# ANALOG_IOUTPUT.net
KiCad netlist of a schematic drawn in Altium Designer
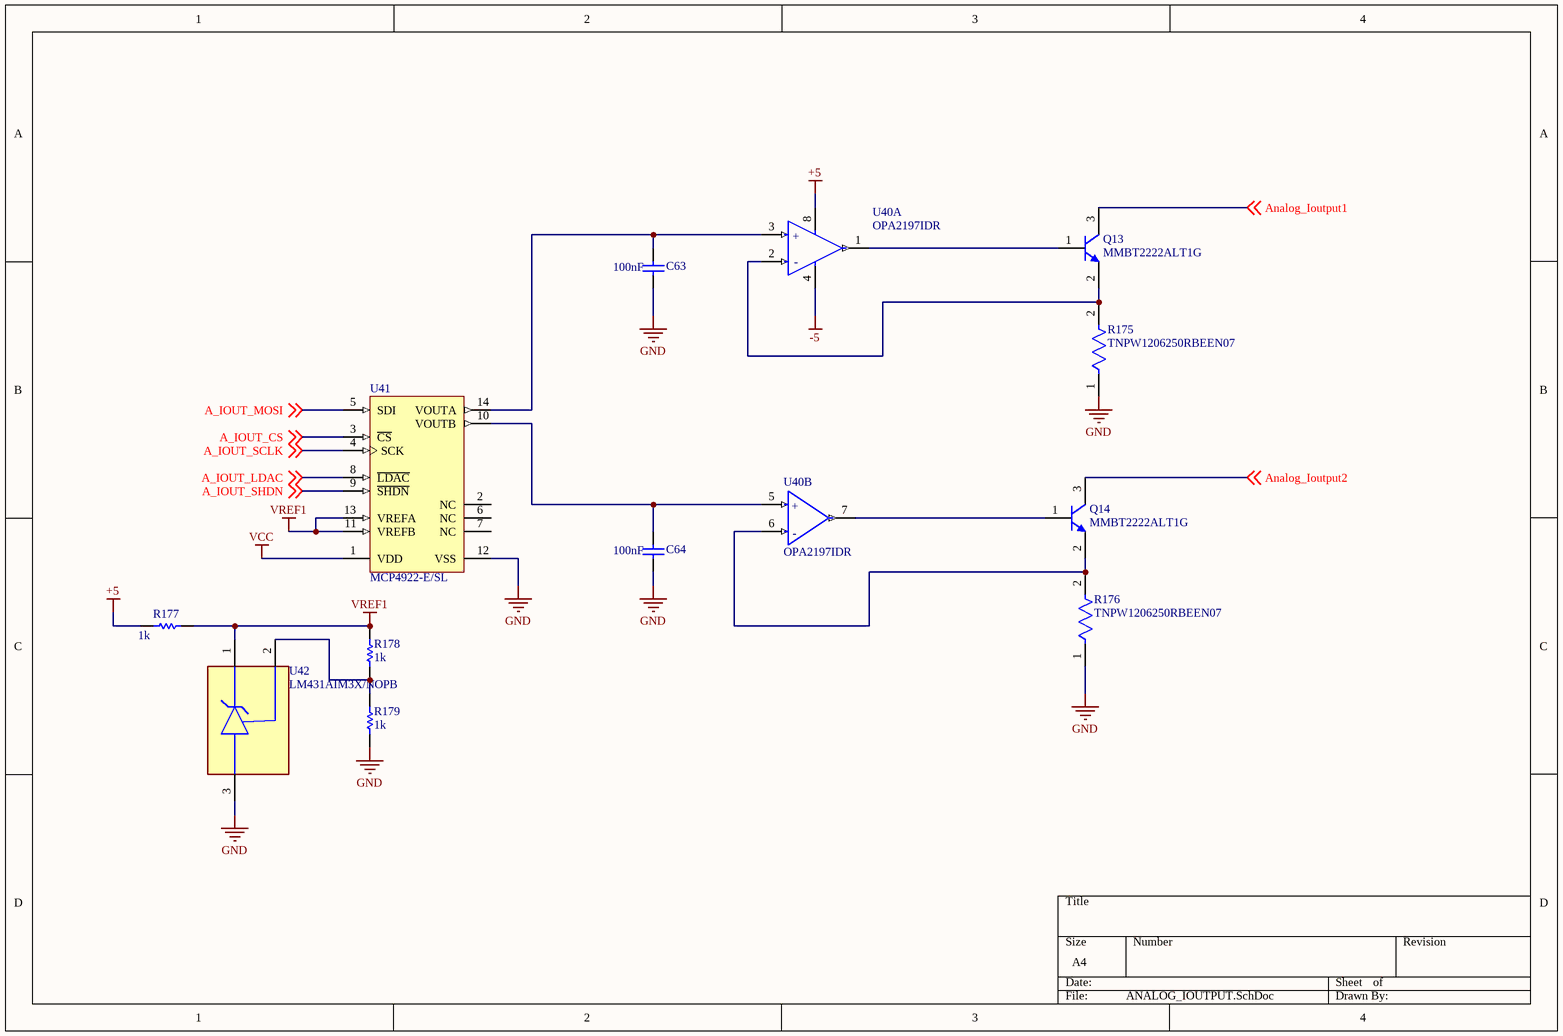
[diagram p0: ANALOG_IOUTPUT.SchDoc]

(export (version "E")
  (design (tool "Eeschema 10.0.6"))
  (components
    (comp (ref "C63")
      (value "GRM21BR71H104KA01L")
      (footprint "CAPC2013X135X45ML10T25")
      (description "Chip Capacitor, 0.1 uF, +/- 10%, 50 V, -55 to 125 degC, 0805 (2012 Metric), RoHS, Tape and Reel")
      (fields
        (field (name "VOLTAGE") "50V")
        (field (name "CAPACITANCE") "100nF")
        (field (name "TOLERANCE") "10%")
      )
      (libsource (lib "Altium Content Vault") (part "CAP-NP-2"))
    )
    (comp (ref "C64")
      (value "GRM21BR71H104KA01L")
      (footprint "CAPC2013X135X45ML10T25")
      (description "Chip Capacitor, 0.1 uF, +/- 10%, 50 V, -55 to 125 degC, 0805 (2012 Metric), RoHS, Tape and Reel")
      (fields
        (field (name "VOLTAGE") "50V")
        (field (name "CAPACITANCE") "100nF")
        (field (name "TOLERANCE") "10%")
      )
      (libsource (lib "Altium Content Vault") (part "CAP-NP-2"))
    )
    (comp (ref "Q13")
      (value "MMBT2222ALT1G")
      (footprint "ONSC-SOT-23-3-318-08_V")
      (description "General Purpose Transistor, NPN Silicon, 3-Pin SOT-23, Pb-Free, Tape and Reel")
      (fields (field (name "MANUFACTURER") "On Semiconductor"))
      (libsource (lib "Altium Content Vault") (part "ONSC-NPN-B1E2C3-3"))
    )
    (comp (ref "Q14")
      (value "MMBT2222ALT1G")
      (footprint "ONSC-SOT-23-3-318-08_V")
      (description "General Purpose Transistor, NPN Silicon, 3-Pin SOT-23, Pb-Free, Tape and Reel")
      (fields (field (name "MANUFACTURER") "On Semiconductor"))
      (libsource (lib "Altium Content Vault") (part "ONSC-NPN-B1E2C3-3"))
    )
    (comp (ref "R175")
      (value "TNPW1206250RBEEN07")
      (footprint "FP-TNPW1206-e3-MFG")
      (description "Res Thnflm 1206 250R Ohm 0.1% 1/4W 25PPM/C SMD")
      (fields (field (name "TOLERANCE") "0.1%"))
      (libsource (lib "Altium Content Vault") (part "1029c3af85768c4190bb7ad29bc67b5"))
    )
    (comp (ref "R176")
      (value "TNPW1206250RBEEN07")
      (footprint "FP-TNPW1206-e3-MFG")
      (description "Res Thnflm 1206 250R Ohm 0.1% 1/4W 25PPM/C SMD")
      (fields (field (name "TOLERANCE") "0.1%"))
      (libsource (lib "Altium Content Vault") (part "1029c3af85768c4190bb7ad29bc67b5"))
    )
    (comp (ref "R177")
      (value "1k")
      (footprint "RESC2013X50X30NL20T20")
      (fields (field (name "MANUFACTURER") "Vishay Dale") (field (name "PART NUMBER") "CRCW08051K00FKTC"))
      (libsource (lib "Altium Content Vault") (part "RES"))
    )
    (comp (ref "R178")
      (value "1k")
      (footprint "RESC2013X50X30NL20T20")
      (fields (field (name "MANUFACTURER") "Vishay Dale") (field (name "PART NUMBER") "CRCW08051K00FKTC"))
      (libsource (lib "Altium Content Vault") (part "RES"))
    )
    (comp (ref "R179")
      (value "1k")
      (footprint "RESC2013X50X30NL20T20")
      (fields (field (name "MANUFACTURER") "Vishay Dale") (field (name "PART NUMBER") "CRCW08051K00FKTC"))
      (libsource (lib "Altium Content Vault") (part "RES"))
    )
    (comp (ref "U40")
      (value "OPA2197IDR")
      (footprint "FP-D0008A-MFG")
      (description "IC OP AMP GP RR 10MHZ 8-SOIC")
      (fields
        (field (name "MANUFACTURER") "Texas Instruments")
        (field (name "OCTOPART") "https://octopart.com/opa2197idr-texas+instruments-75179702")
      )
      (libsource (lib "Altium Content Vault") (part "499df5fc91ff7ad023bcaf249d8becd"))
    )
    (comp (ref "U41")
      (value "MCP4922-E/SL")
      (footprint "SOIC-SL14_M")
      (description "12-Bit DAC with SPI Interface, 14-Pin SOIC 150mil, Extended Temperature")
      (libsource (lib "Altium Content Vault") (part "CON-DAC-MCP4922-14"))
    )
    (comp (ref "U42")
      (value "LM431AIM3X/NOPB")
      (footprint "FP-DBZ0003A-IPC_B")
      (description "IC VREF SHUNT 37V 2.2% SOT23-3")
      (fields (field (name "TOLERANCE") "2%"))
      (libsource (lib "Altium Content Vault") (part "493a0447014da16a84e61b4a2bbdac0"))
    )
  )
  (nets
    (net (code "1") (name "+5") (class "Default")
      (node (ref "R177") (pin "1") (pinfunction "1_1") (pintype "passive"))
      (node (ref "U40") (pin "8") (pinfunction "V+_8") (pintype "power_in"))
    )
    (net (code "2") (name "-5") (class "Default")
      (node (ref "U40") (pin "4") (pinfunction "V-_4") (pintype "power_in"))
    )
    (net (code "3") (name "A_IOUT_CS") (class "Default")
      (node (ref "U41") (pin "3") (pinfunction "~{CS}_3") (pintype "input"))
    )
    (net (code "4") (name "A_IOUT_LDAC") (class "Default")
      (node (ref "U41") (pin "8") (pinfunction "~{LDAC}_8") (pintype "input"))
    )
    (net (code "5") (name "A_IOUT_MOSI") (class "Default")
      (node (ref "U41") (pin "5") (pinfunction "SDI_5") (pintype "input"))
    )
    (net (code "6") (name "A_IOUT_SCLK") (class "Default")
      (node (ref "U41") (pin "4") (pinfunction "SCK_4") (pintype "input"))
    )
    (net (code "7") (name "A_IOUT_SHDN") (class "Default")
      (node (ref "U41") (pin "9") (pinfunction "~{SHDN}_9") (pintype "input"))
    )
    (net (code "8") (name "Analog_Ioutput1") (class "Default")
      (node (ref "Q13") (pin "3") (pinfunction "C_3") (pintype "passive"))
    )
    (net (code "9") (name "Analog_Ioutput2") (class "Default")
      (node (ref "Q14") (pin "3") (pinfunction "C_3") (pintype "passive"))
    )
    (net (code "10") (name "GND") (class "Default")
      (node (ref "C63") (pin "1") (pinfunction "1_1") (pintype "passive"))
      (node (ref "C64") (pin "1") (pinfunction "1_1") (pintype "passive"))
      (node (ref "R175") (pin "1") (pinfunction "1_1") (pintype "passive"))
      (node (ref "R176") (pin "1") (pinfunction "1_1") (pintype "passive"))
      (node (ref "R179") (pin "1") (pinfunction "1_1") (pintype "passive"))
      (node (ref "U41") (pin "12") (pinfunction "VSS_12") (pintype "power_in"))
      (node (ref "U42") (pin "3") (pinfunction "A_3") (pintype "passive"))
    )
    (net (code "11") (name "Net-(Q13-B)") (class "Default")
      (node (ref "Q13") (pin "1") (pinfunction "B_1") (pintype "passive"))
      (node (ref "U40") (pin "1") (pinfunction "OUT_A_1") (pintype "output"))
    )
    (net (code "12") (name "Net-(Q13-E)") (class "Default")
      (node (ref "Q13") (pin "2") (pinfunction "E_2") (pintype "passive"))
      (node (ref "R175") (pin "2") (pinfunction "2_2") (pintype "passive"))
      (node (ref "U40") (pin "2") (pinfunction "-IN_A_2") (pintype "input"))
    )
    (net (code "13") (name "Net-(Q14-B)") (class "Default")
      (node (ref "Q14") (pin "1") (pinfunction "B_1") (pintype "passive"))
      (node (ref "U40") (pin "7") (pinfunction "OUT_B_7") (pintype "output"))
    )
    (net (code "14") (name "Net-(Q14-E)") (class "Default")
      (node (ref "Q14") (pin "2") (pinfunction "E_2") (pintype "passive"))
      (node (ref "R176") (pin "2") (pinfunction "2_2") (pintype "passive"))
      (node (ref "U40") (pin "6") (pinfunction "-IN_B_6") (pintype "input"))
    )
    (net (code "15") (name "Net-(U40A-+IN_A)") (class "Default")
      (node (ref "C63") (pin "2") (pinfunction "2_2") (pintype "passive"))
      (node (ref "U40") (pin "3") (pinfunction "+IN_A_3") (pintype "input"))
      (node (ref "U41") (pin "14") (pinfunction "VOUTA_14") (pintype "output"))
    )
    (net (code "16") (name "Net-(U40B-+IN_B)") (class "Default")
      (node (ref "C64") (pin "2") (pinfunction "2_2") (pintype "passive"))
      (node (ref "U40") (pin "5") (pinfunction "+IN_B_5") (pintype "input"))
      (node (ref "U41") (pin "10") (pinfunction "VOUTB_10") (pintype "output"))
    )
    (net (code "17") (name "Net-(U42-REF)") (class "Default")
      (node (ref "R178") (pin "1") (pinfunction "1_1") (pintype "passive"))
      (node (ref "R179") (pin "2") (pinfunction "2_2") (pintype "passive"))
      (node (ref "U42") (pin "2") (pinfunction "REF_2") (pintype "passive"))
    )
    (net (code "18") (name "VCC") (class "Default")
      (node (ref "U41") (pin "1") (pinfunction "VDD_1") (pintype "power_in"))
    )
    (net (code "19") (name "VREF1") (class "Default")
      (node (ref "R177") (pin "2") (pinfunction "2_2") (pintype "passive"))
      (node (ref "R178") (pin "2") (pinfunction "2_2") (pintype "passive"))
      (node (ref "U41") (pin "11") (pinfunction "VREFB_11") (pintype "input"))
      (node (ref "U41") (pin "13") (pinfunction "VREFA_13") (pintype "input"))
      (node (ref "U42") (pin "1") (pinfunction "C_1") (pintype "passive"))
    )
    (net (code "20") (name "unconnected-(U41-NC-Pad2)") (class "Default")
      (node (ref "U41") (pin "2") (pinfunction "NC_2") (pintype "passive"))
    )
    (net (code "21") (name "unconnected-(U41-NC-Pad6)") (class "Default")
      (node (ref "U41") (pin "6") (pinfunction "NC_6") (pintype "passive"))
    )
    (net (code "22") (name "unconnected-(U41-NC-Pad7)") (class "Default")
      (node (ref "U41") (pin "7") (pinfunction "NC_7") (pintype "passive"))
    )
  )
)
